# PushButtonPower.net
KiCad netlist of a schematic drawn in Altium Designer
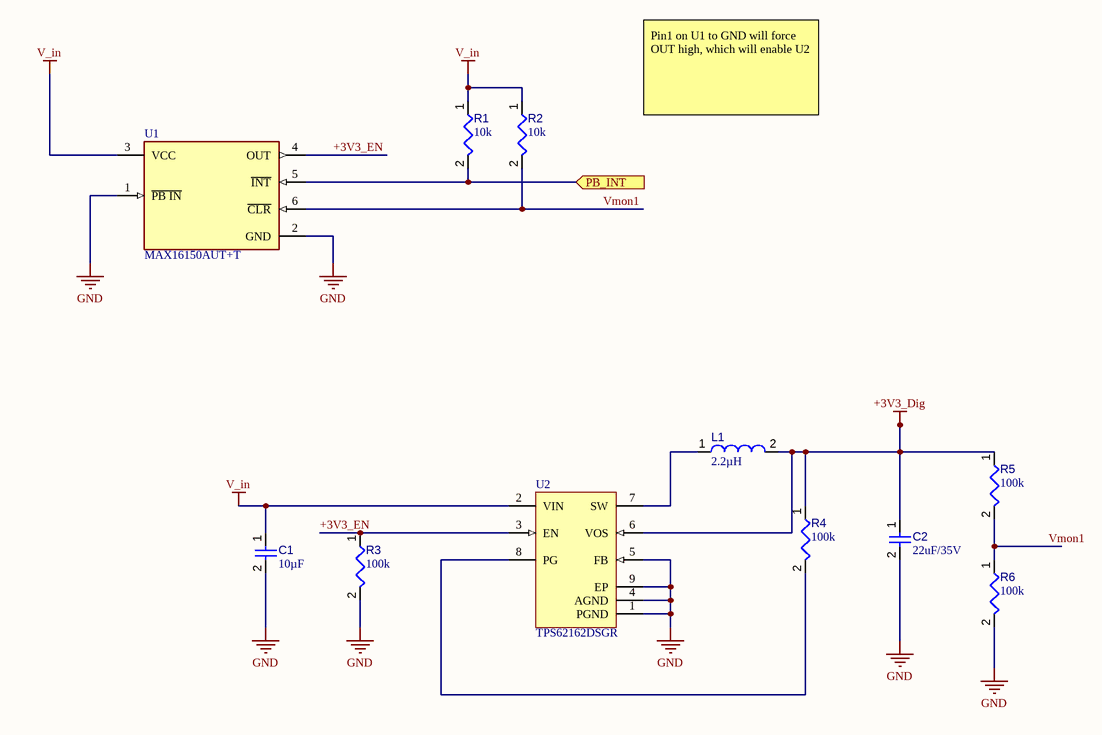
[diagram p0: PushButtonPower.SchDoc]

(export (version "E")
  (design (tool "Eeschema 10.0.6"))
  (components
    (comp (ref "C1")
      (value "10µF")
      (footprint "CAPC0805(2012)145_L")
      (description "Chip Capacitor, 10µF +/-20%, 25V, 0805, Thickness 1.45 mm")
      (fields (field (name "TOLERANCE") "10%") (field (name "Comment") "Capacitor 10µF +/-20% 25V 0805"))
      (libsource (lib "Sreeragaltium_learn") (part "CAP-NP-2"))
    )
    (comp (ref "C2")
      (value "22uF/35V")
      (footprint "CAPC0805(2012)145_L")
      (description "Chip Capacitor, 10µF +/-20%, 25V, 0805, Thickness 1.45 mm")
      (fields (field (name "TOLERANCE") "10%") (field (name "Comment") "Capacitor 10µF +/-20% 25V 0805"))
      (libsource (lib "Sreeragaltium_learn") (part "CAP-NP-2"))
    )
    (comp (ref "L1")
      (value "2.2µH")
      (footprint "INDC2520X100X60NL20T20")
      (description "Chip Inductor, 2.2 uH, +/- 20%, -55 to 125 degC, 1008 (2520 Metric), RoHS, Tape and Reel")
      (fields (field (name "TOLERANCE") "20%") (field (name "MANUFACTURER") "Murata"))
      (libsource (lib "Sreeragaltium_learn") (part "IND-2"))
    )
    (comp (ref "R1")
      (value "10k")
      (footprint "RESC0402(1005)_L")
      (description "Chip Resistor, 10 kOhms, +/-1 %, 63 mW, -55 to 125 degC, 0402")
      (fields (field (name "POWER") "63mW") (field (name "TOLERANCE") "1%"))
      (libsource (lib "Sreeragaltium_learn") (part "RES-2"))
    )
    (comp (ref "R2")
      (value "10k")
      (footprint "RESC0402(1005)_L")
      (description "Chip Resistor, 10 kOhms, +/-1 %, 63 mW, -55 to 125 degC, 0402")
      (fields (field (name "POWER") "63mW") (field (name "TOLERANCE") "1%"))
      (libsource (lib "Sreeragaltium_learn") (part "RES-2"))
    )
    (comp (ref "R3")
      (value "100k")
      (footprint "RESC0402(1005)_L")
      (description "Chip Resistor, 10 kOhms, +/-1 %, 63 mW, -55 to 125 degC, 0402")
      (fields (field (name "POWER") "63mW") (field (name "TOLERANCE") "1%"))
      (libsource (lib "Sreeragaltium_learn") (part "RES-2"))
    )
    (comp (ref "R4")
      (value "100k")
      (footprint "RESC0402(1005)_L")
      (description "Chip Resistor, 10 kOhms, +/-1 %, 63 mW, -55 to 125 degC, 0402")
      (fields (field (name "POWER") "63mW") (field (name "TOLERANCE") "1%"))
      (libsource (lib "Sreeragaltium_learn") (part "RES-2"))
    )
    (comp (ref "R5")
      (value "100k")
      (footprint "RESC0402(1005)_L")
      (description "Chip Resistor, 10 kOhms, +/-1 %, 63 mW, -55 to 125 degC, 0402")
      (fields (field (name "POWER") "63mW") (field (name "TOLERANCE") "1%"))
      (libsource (lib "Sreeragaltium_learn") (part "RES-2"))
    )
    (comp (ref "R6")
      (value "100k")
      (footprint "RESC0402(1005)_L")
      (description "Chip Resistor, 10 kOhms, +/-1 %, 63 mW, -55 to 125 degC, 0402")
      (fields (field (name "POWER") "63mW") (field (name "TOLERANCE") "1%"))
      (libsource (lib "Sreeragaltium_learn") (part "RES-2"))
    )
    (comp (ref "U1")
      (value "MAX16150AUT+T")
      (footprint "FP-U6-1-MFG")
      (description "IC SUPERVISOR 1 CHANNEL SOT23-6")
      (libsource (lib "Altium Content Vault") (part "36a392858d03d148bb8ce7f45f4b5f9"))
    )
    (comp (ref "U2")
      (value "TPS62162DSGR")
      (footprint "DSG0008A_V")
      (fields (field (name "MANUFACTURER") "Texas Instruments"))
      (libsource (lib "Altium Content Vault") (part "TI-TPS62162DSG8-1600X900TP"))
    )
  )
  (nets
    (net (code "1") (name "+3V3_Dig") (class "Default")
      (node (ref "C2") (pin "1") (pinfunction "1_1") (pintype "passive"))
      (node (ref "L1") (pin "2") (pinfunction "2_2") (pintype "passive"))
      (node (ref "R4") (pin "1") (pinfunction "1_1") (pintype "passive"))
      (node (ref "R5") (pin "1") (pinfunction "1_1") (pintype "passive"))
      (node (ref "U2") (pin "6") (pinfunction "VOS_6") (pintype "input"))
    )
    (net (code "2") (name "/+3V3_EN") (class "Default")
      (node (ref "R3") (pin "1") (pinfunction "1_1") (pintype "passive"))
      (node (ref "U1") (pin "4") (pinfunction "OUT_4") (pintype "output"))
      (node (ref "U2") (pin "3") (pinfunction "EN_3") (pintype "input"))
    )
    (net (code "3") (name "/PB_INT") (class "Default")
      (node (ref "R1") (pin "2") (pinfunction "2_2") (pintype "passive"))
      (node (ref "U1") (pin "5") (pinfunction "~{INT}_5") (pintype "input"))
    )
    (net (code "4") (name "/Vmon1") (class "Default")
      (node (ref "R2") (pin "2") (pinfunction "2_2") (pintype "passive"))
      (node (ref "R5") (pin "2") (pinfunction "2_2") (pintype "passive"))
      (node (ref "R6") (pin "1") (pinfunction "1_1") (pintype "passive"))
      (node (ref "U1") (pin "6") (pinfunction "~{CLR}_6") (pintype "input"))
    )
    (net (code "5") (name "GND") (class "Default")
      (node (ref "C1") (pin "2") (pinfunction "2_2") (pintype "passive"))
      (node (ref "C2") (pin "2") (pinfunction "2_2") (pintype "passive"))
      (node (ref "R3") (pin "2") (pinfunction "2_2") (pintype "passive"))
      (node (ref "R6") (pin "2") (pinfunction "2_2") (pintype "passive"))
      (node (ref "U1") (pin "1") (pinfunction "~{PB_IN}_1") (pintype "input"))
      (node (ref "U1") (pin "2") (pinfunction "GND_2") (pintype "power_in"))
      (node (ref "U2") (pin "1") (pinfunction "PGND_1") (pintype "power_in"))
      (node (ref "U2") (pin "4") (pinfunction "AGND_4") (pintype "power_in"))
      (node (ref "U2") (pin "5") (pinfunction "FB_5") (pintype "input"))
      (node (ref "U2") (pin "9") (pinfunction "EP_9") (pintype "power_in"))
    )
    (net (code "6") (name "Net-(U2-PG)") (class "Default")
      (node (ref "R4") (pin "2") (pinfunction "2_2") (pintype "passive"))
      (node (ref "U2") (pin "8") (pinfunction "PG_8") (pintype "tri_state"))
    )
    (net (code "7") (name "Net-(U2-SW)") (class "Default")
      (node (ref "L1") (pin "1") (pinfunction "1_1") (pintype "passive"))
      (node (ref "U2") (pin "7") (pinfunction "SW_7") (pintype "power_in"))
    )
    (net (code "8") (name "V_in") (class "Default")
      (node (ref "C1") (pin "1") (pinfunction "1_1") (pintype "passive"))
      (node (ref "R1") (pin "1") (pinfunction "1_1") (pintype "passive"))
      (node (ref "R2") (pin "1") (pinfunction "1_1") (pintype "passive"))
      (node (ref "U1") (pin "3") (pinfunction "VCC_3") (pintype "power_in"))
      (node (ref "U2") (pin "2") (pinfunction "VIN_2") (pintype "power_in"))
    )
  )
)
